# 2_MCU.net
KiCad netlist of a schematic drawn in Altium Designer
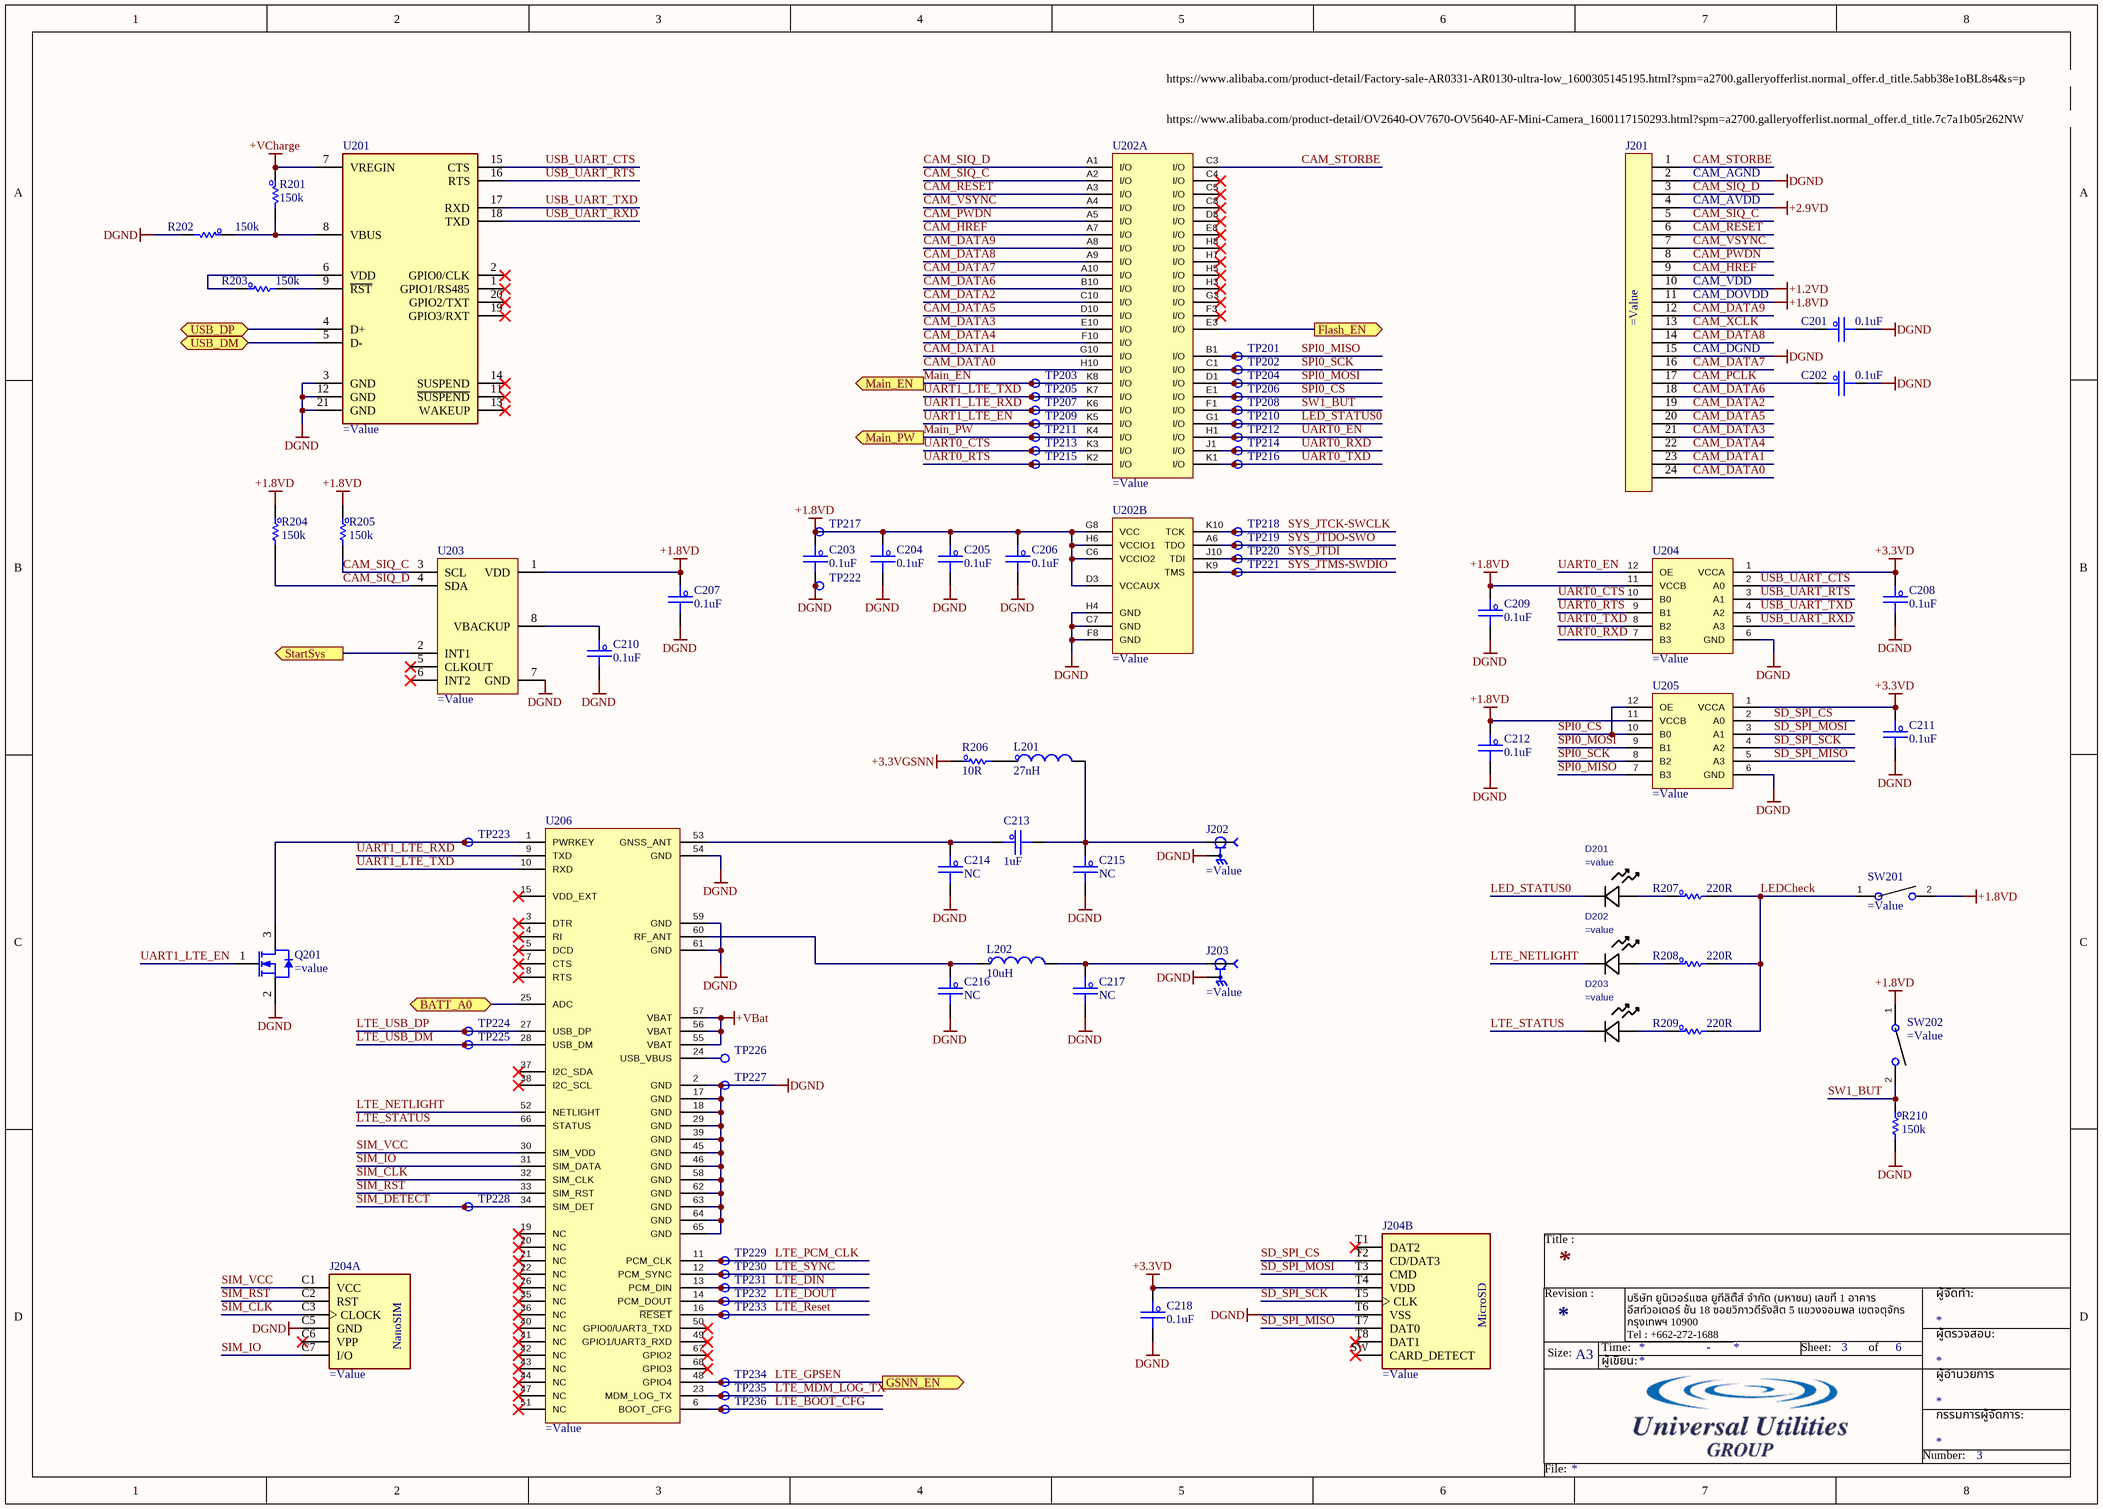
[diagram p0: 2_MCU.SchDoc]

(export (version "E")
  (design (tool "Eeschema 10.0.6"))
  (components
    (comp (ref "C201")
      (value "0.1uF")
      (footprint "C_0603")
      (description "CAP CER 0.1UF 50V X7R 0603")
      (fields (field (name "MANUFACTURER") "KEMET") (field (name "PARTNUMBER") "C0603C104K5RACTU"))
      (libsource (lib "UUSymbol") (part "C_Capacitor"))
    )
    (comp (ref "C202")
      (value "0.1uF")
      (footprint "C_0603")
      (description "CAP CER 0.1UF 50V X7R 0603")
      (fields (field (name "MANUFACTURER") "KEMET") (field (name "PARTNUMBER") "C0603C104K5RACTU"))
      (libsource (lib "UUSymbol") (part "C_Capacitor"))
    )
    (comp (ref "C203")
      (value "0.1uF")
      (footprint "C_0603")
      (description "CAP CER 0.1UF 50V X7R 0603")
      (fields (field (name "MANUFACTURER") "KEMET") (field (name "PARTNUMBER") "C0603C104K5RACTU"))
      (libsource (lib "UUSymbol") (part "C_Capacitor"))
    )
    (comp (ref "C204")
      (value "0.1uF")
      (footprint "C_0603")
      (description "CAP CER 0.1UF 50V X7R 0603")
      (fields (field (name "MANUFACTURER") "KEMET") (field (name "PARTNUMBER") "C0603C104K5RACTU"))
      (libsource (lib "UUSymbol") (part "C_Capacitor"))
    )
    (comp (ref "C205")
      (value "0.1uF")
      (footprint "C_0603")
      (description "CAP CER 0.1UF 50V X7R 0603")
      (fields (field (name "MANUFACTURER") "KEMET") (field (name "PARTNUMBER") "C0603C104K5RACTU"))
      (libsource (lib "UUSymbol") (part "C_Capacitor"))
    )
    (comp (ref "C206")
      (value "0.1uF")
      (footprint "C_0603")
      (description "CAP CER 0.1UF 50V X7R 0603")
      (fields (field (name "MANUFACTURER") "KEMET") (field (name "PARTNUMBER") "C0603C104K5RACTU"))
      (libsource (lib "UUSymbol") (part "C_Capacitor"))
    )
    (comp (ref "C207")
      (value "0.1uF")
      (footprint "C_0603")
      (description "CAP CER 0.1UF 50V X7R 0603")
      (fields (field (name "MANUFACTURER") "KEMET") (field (name "PARTNUMBER") "C0603C104K5RACTU"))
      (libsource (lib "UUSymbol") (part "C_Capacitor"))
    )
    (comp (ref "C208")
      (value "0.1uF")
      (footprint "C_0603")
      (description "CAP CER 0.1UF 50V X7R 0603")
      (fields (field (name "MANUFACTURER") "KEMET") (field (name "PARTNUMBER") "C0603C104K5RACTU"))
      (libsource (lib "UUSymbol") (part "C_Capacitor"))
    )
    (comp (ref "C209")
      (value "0.1uF")
      (footprint "C_0603")
      (description "CAP CER 0.1UF 50V X7R 0603")
      (fields (field (name "MANUFACTURER") "KEMET") (field (name "PARTNUMBER") "C0603C104K5RACTU"))
      (libsource (lib "UUSymbol") (part "C_Capacitor"))
    )
    (comp (ref "C210")
      (value "0.1uF")
      (footprint "C_0603")
      (description "CAP CER 0.1UF 50V X7R 0603")
      (fields (field (name "MANUFACTURER") "KEMET") (field (name "PARTNUMBER") "C0603C104K5RACTU"))
      (libsource (lib "UUSymbol") (part "C_Capacitor"))
    )
    (comp (ref "C211")
      (value "0.1uF")
      (footprint "C_0603")
      (description "CAP CER 0.1UF 50V X7R 0603")
      (fields (field (name "MANUFACTURER") "KEMET") (field (name "PARTNUMBER") "C0603C104K5RACTU"))
      (libsource (lib "UUSymbol") (part "C_Capacitor"))
    )
    (comp (ref "C212")
      (value "0.1uF")
      (footprint "C_0603")
      (description "CAP CER 0.1UF 50V X7R 0603")
      (fields (field (name "MANUFACTURER") "KEMET") (field (name "PARTNUMBER") "C0603C104K5RACTU"))
      (libsource (lib "UUSymbol") (part "C_Capacitor"))
    )
    (comp (ref "C213")
      (value "1uF")
      (footprint "C_0603")
      (description "Capacitor")
      (libsource (lib "UUSymbol") (part "C_Capacitor"))
    )
    (comp (ref "C214")
      (value "NC")
      (footprint "C_0603")
      (description "Capacitor")
      (libsource (lib "UUSymbol") (part "C_Capacitor"))
    )
    (comp (ref "C215")
      (value "NC")
      (footprint "C_0603")
      (description "Capacitor")
      (libsource (lib "UUSymbol") (part "C_Capacitor"))
    )
    (comp (ref "C216")
      (value "NC")
      (footprint "C_0603")
      (description "Capacitor")
      (libsource (lib "UUSymbol") (part "C_Capacitor"))
    )
    (comp (ref "C217")
      (value "NC")
      (footprint "C_0603")
      (description "Capacitor")
      (libsource (lib "UUSymbol") (part "C_Capacitor"))
    )
    (comp (ref "C218")
      (value "0.1uF")
      (footprint "C_0603")
      (description "CAP CER 0.1UF 50V X7R 0603")
      (fields (field (name "MANUFACTURER") "KEMET") (field (name "PARTNUMBER") "C0603C104K5RACTU"))
      (libsource (lib "UUSymbol") (part "C_Capacitor"))
    )
    (comp (ref "D201")
      (value "~")
      (footprint "LED_0VS75000_WRE")
      (description "LED BLUE CLEAR 0603 SMD")
      (fields (field (name "MANUFACTURER") "Wurth Electronics") (field (name "PARTNUMBER") "150060VS75000"))
      (libsource (lib "UUSymbol") (part "D_LED_150060BS75000"))
    )
    (comp (ref "D202")
      (value "~")
      (footprint "LED_0VS75000_WRE")
      (description "LED BLUE CLEAR 0603 SMD")
      (fields (field (name "MANUFACTURER") "Wurth Electronics") (field (name "PARTNUMBER") "150060VS75000"))
      (libsource (lib "UUSymbol") (part "D_LED_150060BS75000"))
    )
    (comp (ref "D203")
      (value "~")
      (footprint "LED_0VS75000_WRE")
      (description "LED BLUE CLEAR 0603 SMD")
      (fields (field (name "MANUFACTURER") "Wurth Electronics") (field (name "PARTNUMBER") "150060VS75000"))
      (libsource (lib "UUSymbol") (part "D_LED_150060BS75000"))
    )
    (comp (ref "J201")
      (value "~")
      (footprint "PANASONIC_AYF532435")
      (description "CONN FFC FPC 24POS 0.50MM R/A")
      (fields
        (field (name "PARTNUMBER") "AYF532435")
        (field (name "MANUFACTURER") "Panasonic Electric Works")
      )
      (libsource (lib "UUSymbol") (part "CON_24P"))
    )
    (comp (ref "J202")
      (value "~")
      (footprint "MOLEX_0734120114")
      (description "CONN UMC RCPT STR 50 OHM SMD")
      (fields (field (name "PARTNUMBER") "0734120114") (field (name "MANUFACTURER") "Molex"))
      (libsource (lib "UUSymbol") (part "CON_U.FL"))
    )
    (comp (ref "J203")
      (value "~")
      (footprint "MOLEX_0734120114")
      (description "CONN UMC RCPT STR 50 OHM SMD")
      (fields (field (name "PARTNUMBER") "0734120114") (field (name "MANUFACTURER") "Molex"))
      (libsource (lib "UUSymbol") (part "CON_U.FL"))
    )
    (comp (ref "J204")
      (value "~")
      (footprint "MOLEX_1042391430")
      (description "IC CPLD 64MC 4.6NS 56BGA")
      (fields (field (name "PARTNUMBER") "XC2C64A-5CP56C") (field (name "MANUFACTURER") "AMD Xilinx"))
      (libsource (lib "UUSymbol") (part "CON_SIMSD_1042391430"))
    )
    (comp (ref "L201")
      (value "27nH")
      (footprint "L_0603")
      (description "10µH Shielded Multilayer Inductor 250mA 1.05Ohm 0603 (1608 Metric)")
      (fields (field (name "MANUFACTURER") "TDK Corporation") (field (name "PARTNUMBER") "MLZ1608M100WT000"))
      (libsource (lib "UUSymbol") (part "L_Inductor"))
    )
    (comp (ref "L202")
      (value "10uH")
      (footprint "L_0603")
      (description "10µH Shielded Multilayer Inductor 250mA 1.05Ohm 0603 (1608 Metric)")
      (fields (field (name "MANUFACTURER") "TDK Corporation") (field (name "PARTNUMBER") "MLZ1608M100WT000"))
      (libsource (lib "UUSymbol") (part "L_Inductor"))
    )
    (comp (ref "Q201")
      (value "~")
      (footprint "SOT95P245X110-3M")
      (description "MOSFET N-CH 60V 300MA SOT23-3")
      (fields
        (field (name "MANUFACTURER") "Infineon Technologies")
        (field (name "PARTNUMBER") "2N7002H6327XTSA2")
      )
      (libsource (lib "UUSymbol") (part "Q_NMOS_2N7002H"))
    )
    (comp (ref "R201")
      (value "150k")
      (footprint "R_0603")
      (description "RES SMD 150K OHM 1% 1/10W 0603")
      (fields (field (name "MANUFACTURER") "Vishay Dale") (field (name "PARTNUMBER") "CRCW0603150KFKEAC"))
      (libsource (lib "UUSymbol") (part "R_Resister"))
    )
    (comp (ref "R202")
      (value "150k")
      (footprint "R_0603")
      (description "RES SMD 150K OHM 1% 1/10W 0603")
      (fields (field (name "MANUFACTURER") "Vishay Dale") (field (name "PARTNUMBER") "CRCW0603150KFKEAC"))
      (libsource (lib "UUSymbol") (part "R_Resister"))
    )
    (comp (ref "R203")
      (value "150k")
      (footprint "R_0603")
      (description "RES SMD 150K OHM 1% 1/10W 0603")
      (fields (field (name "MANUFACTURER") "Vishay Dale") (field (name "PARTNUMBER") "CRCW0603150KFKEAC"))
      (libsource (lib "UUSymbol") (part "R_Resister"))
    )
    (comp (ref "R204")
      (value "150k")
      (footprint "R_0603")
      (description "RES SMD 150K OHM 1% 1/10W 0603")
      (fields (field (name "MANUFACTURER") "Vishay Dale") (field (name "PARTNUMBER") "CRCW0603150KFKEAC"))
      (libsource (lib "UUSymbol") (part "R_Resister"))
    )
    (comp (ref "R205")
      (value "150k")
      (footprint "R_0603")
      (description "RES SMD 150K OHM 1% 1/10W 0603")
      (fields (field (name "MANUFACTURER") "Vishay Dale") (field (name "PARTNUMBER") "CRCW0603150KFKEAC"))
      (libsource (lib "UUSymbol") (part "R_Resister"))
    )
    (comp (ref "R206")
      (value "10R")
      (footprint "R_0603")
      (description "Resistor")
      (fields (field (name "MANUFACTURER") "Vishay") (field (name "PARTNUMBER") "EXB-2HV472JV"))
      (libsource (lib "UUSymbol") (part "R_Resister"))
    )
    (comp (ref "R207")
      (value "220R")
      (footprint "R_0603")
      (description "RES SMD 220 OHM 1% 1/10W 0603")
      (fields (field (name "MANUFACTURER") "Vishay Dale") (field (name "PARTNUMBER") "CRCW0603220RFKEAC"))
      (libsource (lib "UUSymbol") (part "R_Resister"))
    )
    (comp (ref "R208")
      (value "220R")
      (footprint "R_0603")
      (description "RES SMD 220 OHM 1% 1/10W 0603")
      (fields (field (name "MANUFACTURER") "Vishay Dale") (field (name "PARTNUMBER") "CRCW0603220RFKEAC"))
      (libsource (lib "UUSymbol") (part "R_Resister"))
    )
    (comp (ref "R209")
      (value "220R")
      (footprint "R_0603")
      (description "RES SMD 220 OHM 1% 1/10W 0603")
      (fields (field (name "MANUFACTURER") "Vishay Dale") (field (name "PARTNUMBER") "CRCW0603220RFKEAC"))
      (libsource (lib "UUSymbol") (part "R_Resister"))
    )
    (comp (ref "R210")
      (value "150k")
      (footprint "R_0603")
      (description "RES SMD 150K OHM 1% 1/10W 0603")
      (fields (field (name "MANUFACTURER") "Vishay Dale") (field (name "PARTNUMBER") "CRCW0603150KFKEAC"))
      (libsource (lib "UUSymbol") (part "R_Resister"))
    )
    (comp (ref "SW201")
      (value "~")
      (footprint "SW_KSS241GLFS_CN")
      (description "SWITCH TACTILE SPST-NO 0.05A 50V")
      (fields (field (name "PARTNUMBER") "KSS241GLFS") (field (name "MANUFACTURER") "C&K"))
      (libsource (lib "UUSymbol") (part "SW_TAC"))
    )
    (comp (ref "SW202")
      (value "~")
      (footprint "SW_KSS241GLFS_CN")
      (description "SWITCH TACTILE SPST-NO 0.05A 50V")
      (fields (field (name "PARTNUMBER") "KSS241GLFS") (field (name "MANUFACTURER") "C&K"))
      (libsource (lib "UUSymbol") (part "SW_TAC"))
    )
    (comp (ref "TP201")
      (value "~")
      (footprint "TP_Testpoint")
      (description "TestPoint")
      (libsource (lib "UUSymbol") (part "TP_TestPoint"))
    )
    (comp (ref "TP202")
      (value "~")
      (footprint "TP_Testpoint")
      (description "TestPoint")
      (libsource (lib "UUSymbol") (part "TP_TestPoint"))
    )
    (comp (ref "TP203")
      (value "~")
      (footprint "TP_Testpoint")
      (description "TestPoint")
      (libsource (lib "UUSymbol") (part "TP_TestPoint"))
    )
    (comp (ref "TP204")
      (value "~")
      (footprint "TP_Testpoint")
      (description "TestPoint")
      (libsource (lib "UUSymbol") (part "TP_TestPoint"))
    )
    (comp (ref "TP205")
      (value "~")
      (footprint "TP_Testpoint")
      (description "TestPoint")
      (libsource (lib "UUSymbol") (part "TP_TestPoint"))
    )
    (comp (ref "TP206")
      (value "~")
      (footprint "TP_Testpoint")
      (description "TestPoint")
      (libsource (lib "UUSymbol") (part "TP_TestPoint"))
    )
    (comp (ref "TP207")
      (value "~")
      (footprint "TP_Testpoint")
      (description "TestPoint")
      (libsource (lib "UUSymbol") (part "TP_TestPoint"))
    )
    (comp (ref "TP208")
      (value "~")
      (footprint "TP_Testpoint")
      (description "TestPoint")
      (libsource (lib "UUSymbol") (part "TP_TestPoint"))
    )
    (comp (ref "TP209")
      (value "~")
      (footprint "TP_Testpoint")
      (description "TestPoint")
      (libsource (lib "UUSymbol") (part "TP_TestPoint"))
    )
    (comp (ref "TP210")
      (value "~")
      (footprint "TP_Testpoint")
      (description "TestPoint")
      (libsource (lib "UUSymbol") (part "TP_TestPoint"))
    )
    (comp (ref "TP211")
      (value "~")
      (footprint "TP_Testpoint")
      (description "TestPoint")
      (libsource (lib "UUSymbol") (part "TP_TestPoint"))
    )
    (comp (ref "TP212")
      (value "~")
      (footprint "TP_Testpoint")
      (description "TestPoint")
      (libsource (lib "UUSymbol") (part "TP_TestPoint"))
    )
    (comp (ref "TP213")
      (value "~")
      (footprint "TP_Testpoint")
      (description "TestPoint")
      (libsource (lib "UUSymbol") (part "TP_TestPoint"))
    )
    (comp (ref "TP214")
      (value "~")
      (footprint "TP_Testpoint")
      (description "TestPoint")
      (libsource (lib "UUSymbol") (part "TP_TestPoint"))
    )
    (comp (ref "TP215")
      (value "~")
      (footprint "TP_Testpoint")
      (description "TestPoint")
      (libsource (lib "UUSymbol") (part "TP_TestPoint"))
    )
    (comp (ref "TP216")
      (value "~")
      (footprint "TP_Testpoint")
      (description "TestPoint")
      (libsource (lib "UUSymbol") (part "TP_TestPoint"))
    )
    (comp (ref "TP217")
      (value "~")
      (footprint "TP_Testpoint")
      (description "TestPoint")
      (libsource (lib "UUSymbol") (part "TP_TestPoint"))
    )
    (comp (ref "TP218")
      (value "~")
      (footprint "TP_Testpoint")
      (description "TestPoint")
      (libsource (lib "UUSymbol") (part "TP_TestPoint"))
    )
    (comp (ref "TP219")
      (value "~")
      (footprint "TP_Testpoint")
      (description "TestPoint")
      (libsource (lib "UUSymbol") (part "TP_TestPoint"))
    )
    (comp (ref "TP220")
      (value "~")
      (footprint "TP_Testpoint")
      (description "TestPoint")
      (libsource (lib "UUSymbol") (part "TP_TestPoint"))
    )
    (comp (ref "TP221")
      (value "~")
      (footprint "TP_Testpoint")
      (description "TestPoint")
      (libsource (lib "UUSymbol") (part "TP_TestPoint"))
    )
    (comp (ref "TP222")
      (value "~")
      (footprint "TP_Testpoint")
      (description "TestPoint")
      (libsource (lib "UUSymbol") (part "TP_TestPoint"))
    )
    (comp (ref "TP223")
      (value "~")
      (footprint "TP_Testpoint")
      (description "TestPoint")
      (libsource (lib "UUSymbol") (part "TP_TestPoint"))
    )
    (comp (ref "TP224")
      (value "~")
      (footprint "TP_Testpoint")
      (description "TestPoint")
      (libsource (lib "UUSymbol") (part "TP_TestPoint"))
    )
    (comp (ref "TP225")
      (value "~")
      (footprint "TP_Testpoint")
      (description "TestPoint")
      (libsource (lib "UUSymbol") (part "TP_TestPoint"))
    )
    (comp (ref "TP226")
      (value "~")
      (footprint "TP_Testpoint")
      (description "TestPoint")
      (libsource (lib "UUSymbol") (part "TP_TestPoint"))
    )
    (comp (ref "TP227")
      (value "~")
      (footprint "TP_Testpoint")
      (description "TestPoint")
      (libsource (lib "UUSymbol") (part "TP_TestPoint"))
    )
    (comp (ref "TP228")
      (value "~")
      (footprint "TP_Testpoint")
      (description "TestPoint")
      (libsource (lib "UUSymbol") (part "TP_TestPoint"))
    )
    (comp (ref "TP229")
      (value "~")
      (footprint "TP_Testpoint")
      (description "TestPoint")
      (libsource (lib "UUSymbol") (part "TP_TestPoint"))
    )
    (comp (ref "TP230")
      (value "~")
      (footprint "TP_Testpoint")
      (description "TestPoint")
      (libsource (lib "UUSymbol") (part "TP_TestPoint"))
    )
    (comp (ref "TP231")
      (value "~")
      (footprint "TP_Testpoint")
      (description "TestPoint")
      (libsource (lib "UUSymbol") (part "TP_TestPoint"))
    )
    (comp (ref "TP232")
      (value "~")
      (footprint "TP_Testpoint")
      (description "TestPoint")
      (libsource (lib "UUSymbol") (part "TP_TestPoint"))
    )
    (comp (ref "TP233")
      (value "~")
      (footprint "TP_Testpoint")
      (description "TestPoint")
      (libsource (lib "UUSymbol") (part "TP_TestPoint"))
    )
    (comp (ref "TP234")
      (value "~")
      (footprint "TP_Testpoint")
      (description "TestPoint")
      (libsource (lib "UUSymbol") (part "TP_TestPoint"))
    )
    (comp (ref "TP235")
      (value "~")
      (footprint "TP_Testpoint")
      (description "TestPoint")
      (libsource (lib "UUSymbol") (part "TP_TestPoint"))
    )
    (comp (ref "TP236")
      (value "~")
      (footprint "TP_Testpoint")
      (description "TestPoint")
      (libsource (lib "UUSymbol") (part "TP_TestPoint"))
    )
    (comp (ref "U201")
      (value "~")
      (footprint "SILABS_CP2102N-A02-GQFN20R")
      (description "IC USB TO UART BRIDGE QFN20")
      (fields (field (name "PARTNUMBER") "CP2102N-A02-GQFN20") (field (name "MANUFACTURER") "Silicon Labs"))
      (libsource (lib "UUSymbol") (part "IC_USB_CP2102N"))
    )
    (comp (ref "U202")
      (value "~")
      (footprint "CP56_XIL_XC2C64A-5CPG56C")
      (description "IC CPLD 64MC 4.6NS 56BGA")
      (fields (field (name "PARTNUMBER") "XC2C64A-5CP56C") (field (name "MANUFACTURER") "AMD Xilinx"))
      (libsource (lib "UUSymbol") (part "IC_FPGA_XC2C64A"))
    )
    (comp (ref "U203")
      (value "~")
      (footprint "RV8523C3")
      (description "IC RTC CLK/CALENDAR I2C 10SON")
      (fields
        (field (name "PARTNUMBER") "RV-8523-C3-32.768KHZ-20PPM-TA-QC")
        (field (name "MANUFACTURER") "Micro Crystal AG")
      )
      (libsource (lib "UUSymbol") (part "IC_RTC_RV-8523-C3"))
    )
    (comp (ref "U204")
      (value "~")
      (footprint "UMLP12_1P7X2_O00")
      (description "IC TRNSLTR BIDIRECTIONAL 12MLP")
      (fields (field (name "PARTNUMBER") "FXLA0104QFX-F106") (field (name "MANUFACTURER") "onsemi"))
      (libsource (lib "UUSymbol") (part "IC_TRAN_FXLA0104X"))
    )
    (comp (ref "U205")
      (value "~")
      (footprint "UMLP12_1P7X2_O00")
      (description "IC TRNSLTR BIDIRECTIONAL 12MLP")
      (fields (field (name "PARTNUMBER") "FXLA0104QFX-F106") (field (name "MANUFACTURER") "onsemi"))
      (libsource (lib "UUSymbol") (part "IC_TRAN_FXLA0104X"))
    )
    (comp (ref "U206")
      (value "~")
      (footprint "SIM7000A S2-1000")
      (description "DGTL ISO 5000VRMS 6CH 16SOIC")
      (fields
        (field (name "MANUFACTURER") "SIMCom Wireless Solutions Limited")
        (field (name "PARTNUMBER") "SIM7000G")
      )
      (libsource (lib "UUSymbol") (part "IC_MOD_SIM7000X"))
    )
  )
  (nets
    (net (code "1") (name "+1.2VD") (class "Default")
      (node (ref "J201") (pin "10") (pinfunction "10_10") (pintype "passive"))
    )
    (net (code "2") (name "+1.8VD") (class "Default")
      (node (ref "C203") (pin "1") (pinfunction "1_1") (pintype "passive"))
      (node (ref "C204") (pin "1") (pinfunction "1_1") (pintype "passive"))
      (node (ref "C205") (pin "1") (pinfunction "1_1") (pintype "passive"))
      (node (ref "C206") (pin "1") (pinfunction "1_1") (pintype "passive"))
      (node (ref "C207") (pin "1") (pinfunction "1_1") (pintype "passive"))
      (node (ref "C209") (pin "1") (pinfunction "1_1") (pintype "passive"))
      (node (ref "C212") (pin "1") (pinfunction "1_1") (pintype "passive"))
      (node (ref "J201") (pin "11") (pinfunction "11_11") (pintype "passive"))
      (node (ref "R204") (pin "1") (pinfunction "1_1") (pintype "passive"))
      (node (ref "R205") (pin "1") (pinfunction "1_1") (pintype "passive"))
      (node (ref "SW201") (pin "2") (pinfunction "2_2") (pintype "passive"))
      (node (ref "SW202") (pin "1") (pinfunction "1_1") (pintype "passive"))
      (node (ref "TP217") (pin "1") (pinfunction "1_1") (pintype "passive"))
      (node (ref "U202") (pin "C6") (pinfunction "VCCIO2_C6") (pintype "passive"))
      (node (ref "U202") (pin "D3") (pinfunction "VCCAUX_D3") (pintype "passive"))
      (node (ref "U202") (pin "G8") (pinfunction "VCC_G8") (pintype "passive"))
      (node (ref "U202") (pin "H6") (pinfunction "VCCIO1_H6") (pintype "passive"))
      (node (ref "U203") (pin "1") (pinfunction "VDD_1") (pintype "passive"))
      (node (ref "U204") (pin "11") (pinfunction "VCCB_11") (pintype "passive"))
      (node (ref "U205") (pin "11") (pinfunction "VCCB_11") (pintype "passive"))
    )
    (net (code "3") (name "+2.9VD") (class "Default")
      (node (ref "J201") (pin "4") (pinfunction "4_4") (pintype "passive"))
    )
    (net (code "4") (name "+3.3VD") (class "Default")
      (node (ref "C208") (pin "1") (pinfunction "1_1") (pintype "passive"))
      (node (ref "C211") (pin "1") (pinfunction "1_1") (pintype "passive"))
      (node (ref "C218") (pin "1") (pinfunction "1_1") (pintype "passive"))
      (node (ref "J204") (pin "T4") (pinfunction "VDD_T4") (pintype "passive"))
      (node (ref "U204") (pin "1") (pinfunction "VCCA_1") (pintype "passive"))
      (node (ref "U205") (pin "1") (pinfunction "VCCA_1") (pintype "passive"))
    )
    (net (code "5") (name "+3.3VGSNN") (class "Default")
      (node (ref "R206") (pin "1") (pinfunction "1_1") (pintype "passive"))
    )
    (net (code "6") (name "+VBat") (class "Default")
      (node (ref "U206") (pin "55") (pinfunction "VBAT_55") (pintype "passive"))
      (node (ref "U206") (pin "56") (pinfunction "VBAT_56") (pintype "passive"))
      (node (ref "U206") (pin "57") (pinfunction "VBAT_57") (pintype "passive"))
    )
    (net (code "7") (name "+VCharge") (class "Default")
      (node (ref "R201") (pin "1") (pinfunction "1_1") (pintype "passive"))
      (node (ref "U201") (pin "7") (pinfunction "VREGIN_7") (pintype "passive"))
    )
    (net (code "8") (name "/BATT_A0") (class "Default")
      (node (ref "U206") (pin "25") (pinfunction "ADC_25") (pintype "passive"))
    )
    (net (code "9") (name "/CAM_DATA0") (class "Default")
      (node (ref "J201") (pin "24") (pinfunction "24_24") (pintype "passive"))
      (node (ref "U202") (pin "H10") (pinfunction "I/O_H10") (pintype "passive"))
    )
    (net (code "10") (name "/CAM_DATA1") (class "Default")
      (node (ref "J201") (pin "23") (pinfunction "23_23") (pintype "passive"))
      (node (ref "U202") (pin "G10") (pinfunction "I/O_G10") (pintype "passive"))
    )
    (net (code "11") (name "/CAM_DATA2") (class "Default")
      (node (ref "J201") (pin "19") (pinfunction "19_19") (pintype "passive"))
      (node (ref "U202") (pin "C10") (pinfunction "I/O_C10") (pintype "passive"))
    )
    (net (code "12") (name "/CAM_DATA3") (class "Default")
      (node (ref "J201") (pin "21") (pinfunction "21_21") (pintype "passive"))
      (node (ref "U202") (pin "E10") (pinfunction "I/O_E10") (pintype "passive"))
    )
    (net (code "13") (name "/CAM_DATA4") (class "Default")
      (node (ref "J201") (pin "22") (pinfunction "22_22") (pintype "passive"))
      (node (ref "U202") (pin "F10") (pinfunction "I/O_F10") (pintype "passive"))
    )
    (net (code "14") (name "/CAM_DATA5") (class "Default")
      (node (ref "J201") (pin "20") (pinfunction "20_20") (pintype "passive"))
      (node (ref "U202") (pin "D10") (pinfunction "I/O_D10") (pintype "passive"))
    )
    (net (code "15") (name "/CAM_DATA6") (class "Default")
      (node (ref "J201") (pin "18") (pinfunction "18_18") (pintype "passive"))
      (node (ref "U202") (pin "B10") (pinfunction "I/O_B10") (pintype "passive"))
    )
    (net (code "16") (name "/CAM_DATA7") (class "Default")
      (node (ref "J201") (pin "16") (pinfunction "16_16") (pintype "passive"))
      (node (ref "U202") (pin "A10") (pinfunction "I/O_A10") (pintype "passive"))
    )
    (net (code "17") (name "/CAM_DATA8") (class "Default")
      (node (ref "J201") (pin "14") (pinfunction "14_14") (pintype "passive"))
      (node (ref "U202") (pin "A9") (pinfunction "I/O_A9") (pintype "passive"))
    )
    (net (code "18") (name "/CAM_DATA9") (class "Default")
      (node (ref "J201") (pin "12") (pinfunction "12_12") (pintype "passive"))
      (node (ref "U202") (pin "A8") (pinfunction "I/O_A8") (pintype "passive"))
    )
    (net (code "19") (name "/CAM_HREF") (class "Default")
      (node (ref "J201") (pin "9") (pinfunction "9_9") (pintype "passive"))
      (node (ref "U202") (pin "A7") (pinfunction "I/O_A7") (pintype "passive"))
    )
    (net (code "20") (name "/CAM_PCLK") (class "Default")
      (node (ref "C202") (pin "1") (pinfunction "1_1") (pintype "passive"))
      (node (ref "J201") (pin "17") (pinfunction "17_17") (pintype "passive"))
    )
    (net (code "21") (name "/CAM_PWDN") (class "Default")
      (node (ref "J201") (pin "8") (pinfunction "8_8") (pintype "passive"))
      (node (ref "U202") (pin "A5") (pinfunction "I/O_A5") (pintype "passive"))
    )
    (net (code "22") (name "/CAM_RESET") (class "Default")
      (node (ref "J201") (pin "6") (pinfunction "6_6") (pintype "passive"))
      (node (ref "U202") (pin "A3") (pinfunction "I/O_A3") (pintype "passive"))
    )
    (net (code "23") (name "/CAM_SIQ_C") (class "Default")
      (node (ref "J201") (pin "5") (pinfunction "5_5") (pintype "passive"))
      (node (ref "R205") (pin "2") (pinfunction "2_2") (pintype "passive"))
      (node (ref "U202") (pin "A2") (pinfunction "I/O_A2") (pintype "passive"))
      (node (ref "U203") (pin "3") (pinfunction "SCL_3") (pintype "passive"))
    )
    (net (code "24") (name "/CAM_SIQ_D") (class "Default")
      (node (ref "J201") (pin "3") (pinfunction "3_3") (pintype "passive"))
      (node (ref "R204") (pin "2") (pinfunction "2_2") (pintype "passive"))
      (node (ref "U202") (pin "A1") (pinfunction "I/O_A1") (pintype "passive"))
      (node (ref "U203") (pin "4") (pinfunction "SDA_4") (pintype "passive"))
    )
    (net (code "25") (name "/CAM_STORBE") (class "Default")
      (node (ref "J201") (pin "1") (pinfunction "1_1") (pintype "passive"))
      (node (ref "U202") (pin "C3") (pinfunction "I/O_C3") (pintype "passive"))
    )
    (net (code "26") (name "/CAM_VSYNC") (class "Default")
      (node (ref "J201") (pin "7") (pinfunction "7_7") (pintype "passive"))
      (node (ref "U202") (pin "A4") (pinfunction "I/O_A4") (pintype "passive"))
    )
    (net (code "27") (name "/CAM_XCLK") (class "Default")
      (node (ref "C201") (pin "1") (pinfunction "1_1") (pintype "passive"))
      (node (ref "J201") (pin "13") (pinfunction "13_13") (pintype "passive"))
    )
    (net (code "28") (name "/Flash_EN") (class "Default")
      (node (ref "U202") (pin "E3") (pinfunction "I/O_E3") (pintype "passive"))
    )
    (net (code "29") (name "/LEDCheck") (class "Default")
      (node (ref "R207") (pin "2") (pinfunction "2_2") (pintype "passive"))
      (node (ref "R208") (pin "2") (pinfunction "2_2") (pintype "passive"))
      (node (ref "R209") (pin "2") (pinfunction "2_2") (pintype "passive"))
      (node (ref "SW201") (pin "1") (pinfunction "1_1") (pintype "passive"))
    )
    (net (code "30") (name "/LED_STATUS0") (class "Default")
      (node (ref "D201") (pin "2") (pinfunction "2_2") (pintype "passive"))
      (node (ref "TP210") (pin "1") (pinfunction "1_1") (pintype "passive"))
      (node (ref "U202") (pin "G1") (pinfunction "I/O_G1") (pintype "passive"))
    )
    (net (code "31") (name "/LTE_BOOT_CFG") (class "Default")
      (node (ref "TP236") (pin "1") (pinfunction "1_1") (pintype "passive"))
      (node (ref "U206") (pin "6") (pinfunction "BOOT_CFG_6") (pintype "passive"))
    )
    (net (code "32") (name "/LTE_DIN") (class "Default")
      (node (ref "TP231") (pin "1") (pinfunction "1_1") (pintype "passive"))
      (node (ref "U206") (pin "13") (pinfunction "PCM_DIN_13") (pintype "passive"))
    )
    (net (code "33") (name "/LTE_DOUT") (class "Default")
      (node (ref "TP232") (pin "1") (pinfunction "1_1") (pintype "passive"))
      (node (ref "U206") (pin "14") (pinfunction "PCM_DOUT_14") (pintype "passive"))
    )
    (net (code "34") (name "/LTE_GPSEN") (class "Default")
      (node (ref "TP234") (pin "1") (pinfunction "1_1") (pintype "passive"))
      (node (ref "U206") (pin "48") (pinfunction "GPIO4_48") (pintype "passive"))
    )
    (net (code "35") (name "/LTE_MDM_LOG_TX") (class "Default")
      (node (ref "TP235") (pin "1") (pinfunction "1_1") (pintype "passive"))
      (node (ref "U206") (pin "23") (pinfunction "MDM_LOG_TX_23") (pintype "passive"))
    )
    (net (code "36") (name "/LTE_NETLIGHT") (class "Default")
      (node (ref "D202") (pin "2") (pinfunction "2_2") (pintype "passive"))
      (node (ref "U206") (pin "52") (pinfunction "NETLIGHT_52") (pintype "passive"))
    )
    (net (code "37") (name "/LTE_PCM_CLK") (class "Default")
      (node (ref "TP229") (pin "1") (pinfunction "1_1") (pintype "passive"))
      (node (ref "U206") (pin "11") (pinfunction "PCM_CLK_11") (pintype "passive"))
    )
    (net (code "38") (name "/LTE_Reset") (class "Default")
      (node (ref "TP233") (pin "1") (pinfunction "1_1") (pintype "passive"))
      (node (ref "U206") (pin "16") (pinfunction "~{RESET}_16") (pintype "passive"))
    )
    (net (code "39") (name "/LTE_STATUS") (class "Default")
      (node (ref "D203") (pin "2") (pinfunction "2_2") (pintype "passive"))
      (node (ref "U206") (pin "66") (pinfunction "STATUS_66") (pintype "passive"))
    )
    (net (code "40") (name "/LTE_SYNC") (class "Default")
      (node (ref "TP230") (pin "1") (pinfunction "1_1") (pintype "passive"))
      (node (ref "U206") (pin "12") (pinfunction "PCM_SYNC_12") (pintype "passive"))
    )
    (net (code "41") (name "/LTE_USB_DM") (class "Default")
      (node (ref "TP225") (pin "1") (pinfunction "1_1") (pintype "passive"))
      (node (ref "U206") (pin "28") (pinfunction "USB_DM_28") (pintype "passive"))
    )
    (net (code "42") (name "/LTE_USB_DP") (class "Default")
      (node (ref "TP224") (pin "1") (pinfunction "1_1") (pintype "passive"))
      (node (ref "U206") (pin "27") (pinfunction "USB_DP_27") (pintype "passive"))
    )
    (net (code "43") (name "/Main_EN") (class "Default")
      (node (ref "TP203") (pin "1") (pinfunction "1_1") (pintype "passive"))
      (node (ref "U202") (pin "K8") (pinfunction "I/O_K8") (pintype "passive"))
    )
    (net (code "44") (name "/Main_PW") (class "Default")
      (node (ref "TP211") (pin "1") (pinfunction "1_1") (pintype "passive"))
      (node (ref "U202") (pin "K4") (pinfunction "I/O_K4") (pintype "passive"))
    )
    (net (code "45") (name "/SD_SPI_CS") (class "Default")
      (node (ref "J204") (pin "T2") (pinfunction "CD/DAT3_T2") (pintype "passive"))
      (node (ref "U205") (pin "2") (pinfunction "A0_2") (pintype "passive"))
    )
    (net (code "46") (name "/SD_SPI_MISO") (class "Default")
      (node (ref "J204") (pin "T7") (pinfunction "DAT0_T7") (pintype "passive"))
      (node (ref "U205") (pin "5") (pinfunction "A3_5") (pintype "passive"))
    )
    (net (code "47") (name "/SD_SPI_MOSI") (class "Default")
      (node (ref "J204") (pin "T3") (pinfunction "CMD_T3") (pintype "passive"))
      (node (ref "U205") (pin "3") (pinfunction "A1_3") (pintype "passive"))
    )
    (net (code "48") (name "/SD_SPI_SCK") (class "Default")
      (node (ref "J204") (pin "T5") (pinfunction "CLK_T5") (pintype "passive"))
      (node (ref "U205") (pin "4") (pinfunction "A2_4") (pintype "passive"))
    )
    (net (code "49") (name "/SIM_CLK") (class "Default")
      (node (ref "J204") (pin "C3") (pinfunction "CLOCK_C3") (pintype "passive"))
      (node (ref "U206") (pin "32") (pinfunction "SIM_CLK_32") (pintype "passive"))
    )
    (net (code "50") (name "/SIM_DETECT") (class "Default")
      (node (ref "TP228") (pin "1") (pinfunction "1_1") (pintype "passive"))
      (node (ref "U206") (pin "34") (pinfunction "SIM_DET_34") (pintype "passive"))
    )
    (net (code "51") (name "/SIM_IO") (class "Default")
      (node (ref "J204") (pin "C7") (pinfunction "I/O_C7") (pintype "passive"))
      (node (ref "U206") (pin "31") (pinfunction "SIM_DATA_31") (pintype "passive"))
    )
    (net (code "52") (name "/SIM_RST") (class "Default")
      (node (ref "J204") (pin "C2") (pinfunction "RST_C2") (pintype "passive"))
      (node (ref "U206") (pin "33") (pinfunction "SIM_RST_33") (pintype "passive"))
    )
    (net (code "53") (name "/SIM_VCC") (class "Default")
      (node (ref "J204") (pin "C1") (pinfunction "VCC_C1") (pintype "passive"))
      (node (ref "U206") (pin "30") (pinfunction "SIM_VDD_30") (pintype "passive"))
    )
    (net (code "54") (name "/SPI0_CS") (class "Default")
      (node (ref "TP206") (pin "1") (pinfunction "1_1") (pintype "passive"))
      (node (ref "U202") (pin "E1") (pinfunction "I/O_E1") (pintype "passive"))
      (node (ref "U205") (pin "10") (pinfunction "B0_10") (pintype "passive"))
      (node (ref "U205") (pin "12") (pinfunction "OE_12") (pintype "passive"))
    )
    (net (code "55") (name "/SPI0_MISO") (class "Default")
      (node (ref "TP201") (pin "1") (pinfunction "1_1") (pintype "passive"))
      (node (ref "U202") (pin "B1") (pinfunction "I/O_B1") (pintype "passive"))
      (node (ref "U205") (pin "7") (pinfunction "B3_7") (pintype "passive"))
    )
    (net (code "56") (name "/SPI0_MOSI") (class "Default")
      (node (ref "TP204") (pin "1") (pinfunction "1_1") (pintype "passive"))
      (node (ref "U202") (pin "D1") (pinfunction "I/O_D1") (pintype "passive"))
      (node (ref "U205") (pin "9") (pinfunction "B1_9") (pintype "passive"))
    )
    (net (code "57") (name "/SPI0_SCK") (class "Default")
      (node (ref "TP202") (pin "1") (pinfunction "1_1") (pintype "passive"))
      (node (ref "U202") (pin "C1") (pinfunction "I/O_C1") (pintype "passive"))
      (node (ref "U205") (pin "8") (pinfunction "B2_8") (pintype "passive"))
    )
    (net (code "58") (name "/SW1_BUT") (class "Default")
      (node (ref "R210") (pin "1") (pinfunction "1_1") (pintype "passive"))
      (node (ref "SW202") (pin "2") (pinfunction "2_2") (pintype "passive"))
      (node (ref "TP208") (pin "1") (pinfunction "1_1") (pintype "passive"))
      (node (ref "U202") (pin "F1") (pinfunction "I/O_F1") (pintype "passive"))
    )
    (net (code "59") (name "/SYS_JTCK-SWCLK") (class "Default")
      (node (ref "TP218") (pin "1") (pinfunction "1_1") (pintype "passive"))
      (node (ref "U202") (pin "K10") (pinfunction "TCK_K10") (pintype "passive"))
    )
    (net (code "60") (name "/SYS_JTDI") (class "Default")
      (node (ref "TP220") (pin "1") (pinfunction "1_1") (pintype "passive"))
      (node (ref "U202") (pin "J10") (pinfunction "TDI_J10") (pintype "passive"))
    )
    (net (code "61") (name "/SYS_JTDO-SWO") (class "Default")
      (node (ref "TP219") (pin "1") (pinfunction "1_1") (pintype "passive"))
      (node (ref "U202") (pin "A6") (pinfunction "TDO_A6") (pintype "passive"))
    )
    (net (code "62") (name "/SYS_JTMS-SWDIO") (class "Default")
      (node (ref "TP221") (pin "1") (pinfunction "1_1") (pintype "passive"))
      (node (ref "U202") (pin "K9") (pinfunction "TMS_K9") (pintype "passive"))
    )
    (net (code "63") (name "/StartSys") (class "Default")
      (node (ref "U203") (pin "2") (pinfunction "INT1_2") (pintype "passive"))
    )
    (net (code "64") (name "/UART0_CTS") (class "Default")
      (node (ref "TP213") (pin "1") (pinfunction "1_1") (pintype "passive"))
      (node (ref "U202") (pin "K3") (pinfunction "I/O_K3") (pintype "passive"))
      (node (ref "U204") (pin "10") (pinfunction "B0_10") (pintype "passive"))
    )
    (net (code "65") (name "/UART0_EN") (class "Default")
      (node (ref "TP212") (pin "1") (pinfunction "1_1") (pintype "passive"))
      (node (ref "U202") (pin "H1") (pinfunction "I/O_H1") (pintype "passive"))
      (node (ref "U204") (pin "12") (pinfunction "OE_12") (pintype "passive"))
    )
    (net (code "66") (name "/UART0_RTS") (class "Default")
      (node (ref "TP215") (pin "1") (pinfunction "1_1") (pintype "passive"))
      (node (ref "U202") (pin "K2") (pinfunction "I/O_K2") (pintype "passive"))
      (node (ref "U204") (pin "9") (pinfunction "B1_9") (pintype "passive"))
    )
    (net (code "67") (name "/UART0_RXD") (class "Default")
      (node (ref "TP214") (pin "1") (pinfunction "1_1") (pintype "passive"))
      (node (ref "U202") (pin "J1") (pinfunction "I/O_J1") (pintype "passive"))
      (node (ref "U204") (pin "7") (pinfunction "B3_7") (pintype "passive"))
    )
    (net (code "68") (name "/UART0_TXD") (class "Default")
      (node (ref "TP216") (pin "1") (pinfunction "1_1") (pintype "passive"))
      (node (ref "U202") (pin "K1") (pinfunction "I/O_K1") (pintype "passive"))
      (node (ref "U204") (pin "8") (pinfunction "B2_8") (pintype "passive"))
    )
    (net (code "69") (name "/UART1_LTE_EN") (class "Default")
      (node (ref "Q201") (pin "1") (pinfunction "G_1") (pintype "passive"))
      (node (ref "TP209") (pin "1") (pinfunction "1_1") (pintype "passive"))
      (node (ref "U202") (pin "K5") (pinfunction "I/O_K5") (pintype "passive"))
    )
    (net (code "70") (name "/UART1_LTE_RXD") (class "Default")
      (node (ref "TP207") (pin "1") (pinfunction "1_1") (pintype "passive"))
      (node (ref "U202") (pin "K6") (pinfunction "I/O_K6") (pintype "passive"))
      (node (ref "U206") (pin "9") (pinfunction "TXD_9") (pintype "passive"))
    )
    (net (code "71") (name "/UART1_LTE_TXD") (class "Default")
      (node (ref "TP205") (pin "1") (pinfunction "1_1") (pintype "passive"))
      (node (ref "U202") (pin "K7") (pinfunction "I/O_K7") (pintype "passive"))
      (node (ref "U206") (pin "10") (pinfunction "RXD_10") (pintype "passive"))
    )
    (net (code "72") (name "/USB_DM") (class "Default")
      (node (ref "U201") (pin "5") (pinfunction "D-_5") (pintype "passive"))
    )
    (net (code "73") (name "/USB_DP") (class "Default")
      (node (ref "U201") (pin "4") (pinfunction "D+_4") (pintype "passive"))
    )
    (net (code "74") (name "/USB_UART_CTS") (class "Default")
      (node (ref "U201") (pin "15") (pinfunction "CTS_15") (pintype "passive"))
      (node (ref "U204") (pin "2") (pinfunction "A0_2") (pintype "passive"))
    )
    (net (code "75") (name "/USB_UART_RTS") (class "Default")
      (node (ref "U201") (pin "16") (pinfunction "RTS_16") (pintype "passive"))
      (node (ref "U204") (pin "3") (pinfunction "A1_3") (pintype "passive"))
    )
    (net (code "76") (name "/USB_UART_RXD") (class "Default")
      (node (ref "U201") (pin "18") (pinfunction "TXD_18") (pintype "passive"))
      (node (ref "U204") (pin "5") (pinfunction "A3_5") (pintype "passive"))
    )
    (net (code "77") (name "/USB_UART_TXD") (class "Default")
      (node (ref "U201") (pin "17") (pinfunction "RXD_17") (pintype "passive"))
      (node (ref "U204") (pin "4") (pinfunction "A2_4") (pintype "passive"))
    )
    (net (code "78") (name "DGND") (class "Default")
      (node (ref "C201") (pin "2") (pinfunction "2_2") (pintype "passive"))
      (node (ref "C202") (pin "2") (pinfunction "2_2") (pintype "passive"))
      (node (ref "C203") (pin "2") (pinfunction "2_2") (pintype "passive"))
      (node (ref "C204") (pin "2") (pinfunction "2_2") (pintype "passive"))
      (node (ref "C205") (pin "2") (pinfunction "2_2") (pintype "passive"))
      (node (ref "C206") (pin "2") (pinfunction "2_2") (pintype "passive"))
      (node (ref "C207") (pin "2") (pinfunction "2_2") (pintype "passive"))
      (node (ref "C208") (pin "2") (pinfunction "2_2") (pintype "passive"))
      (node (ref "C209") (pin "2") (pinfunction "2_2") (pintype "passive"))
      (node (ref "C210") (pin "2") (pinfunction "2_2") (pintype "passive"))
      (node (ref "C211") (pin "2") (pinfunction "2_2") (pintype "passive"))
      (node (ref "C212") (pin "2") (pinfunction "2_2") (pintype "passive"))
      (node (ref "C214") (pin "2") (pinfunction "2_2") (pintype "passive"))
      (node (ref "C215") (pin "2") (pinfunction "2_2") (pintype "passive"))
      (node (ref "C216") (pin "2") (pinfunction "2_2") (pintype "passive"))
      (node (ref "C217") (pin "2") (pinfunction "2_2") (pintype "passive"))
      (node (ref "C218") (pin "2") (pinfunction "2_2") (pintype "passive"))
      (node (ref "J201") (pin "15") (pinfunction "15_15") (pintype "passive"))
      (node (ref "J201") (pin "2") (pinfunction "2_2") (pintype "passive"))
      (node (ref "J202") (pin "2") (pinfunction "2_2") (pintype "passive"))
      (node (ref "J203") (pin "2") (pinfunction "2_2") (pintype "passive"))
      (node (ref "J204") (pin "C5") (pinfunction "GND_C5") (pintype "passive"))
      (node (ref "J204") (pin "T6") (pinfunction "VSS_T6") (pintype "passive"))
      (node (ref "Q201") (pin "2") (pinfunction "S_2") (pintype "passive"))
      (node (ref "R202") (pin "2") (pinfunction "2_2") (pintype "passive"))
      (node (ref "R210") (pin "2") (pinfunction "2_2") (pintype "passive"))
      (node (ref "TP222") (pin "1") (pinfunction "1_1") (pintype "passive"))
      (node (ref "TP227") (pin "1") (pinfunction "1_1") (pintype "passive"))
      (node (ref "U201") (pin "12") (pinfunction "GND_12") (pintype "passive"))
      (node (ref "U201") (pin "21") (pinfunction "GND_21") (pintype "passive"))
      (node (ref "U201") (pin "3") (pinfunction "GND_3") (pintype "passive"))
      (node (ref "U202") (pin "C7") (pinfunction "GND_C7") (pintype "passive"))
      (node (ref "U202") (pin "F8") (pinfunction "GND_F8") (pintype "passive"))
      (node (ref "U202") (pin "H4") (pinfunction "GND_H4") (pintype "passive"))
      (node (ref "U203") (pin "7") (pinfunction "GND_7") (pintype "passive"))
      (node (ref "U204") (pin "6") (pinfunction "GND_6") (pintype "passive"))
      (node (ref "U205") (pin "6") (pinfunction "GND_6") (pintype "passive"))
      (node (ref "U206") (pin "17") (pinfunction "GND_17") (pintype "passive"))
      (node (ref "U206") (pin "18") (pinfunction "GND_18") (pintype "passive"))
      (node (ref "U206") (pin "2") (pinfunction "GND_2") (pintype "passive"))
      (node (ref "U206") (pin "29") (pinfunction "GND_29") (pintype "passive"))
      (node (ref "U206") (pin "39") (pinfunction "GND_39") (pintype "passive"))
      (node (ref "U206") (pin "45") (pinfunction "GND_45") (pintype "passive"))
      (node (ref "U206") (pin "46") (pinfunction "GND_46") (pintype "passive"))
      (node (ref "U206") (pin "54") (pinfunction "GND_54") (pintype "passive"))
      (node (ref "U206") (pin "58") (pinfunction "GND_58") (pintype "passive"))
      (node (ref "U206") (pin "59") (pinfunction "GND_59") (pintype "passive"))
      (node (ref "U206") (pin "61") (pinfunction "GND_61") (pintype "passive"))
      (node (ref "U206") (pin "62") (pinfunction "GND_62") (pintype "passive"))
      (node (ref "U206") (pin "63") (pinfunction "GND_63") (pintype "passive"))
      (node (ref "U206") (pin "64") (pinfunction "GND_64") (pintype "passive"))
      (node (ref "U206") (pin "65") (pinfunction "GND_65") (pintype "passive"))
    )
    (net (code "79") (name "Net-(C213-Pad2)") (class "Default")
      (node (ref "C213") (pin "2") (pinfunction "2_2") (pintype "passive"))
      (node (ref "C215") (pin "1") (pinfunction "1_1") (pintype "passive"))
      (node (ref "J202") (pin "1") (pinfunction "1_1") (pintype "passive"))
      (node (ref "L201") (pin "2") (pinfunction "2_2") (pintype "passive"))
    )
    (net (code "80") (name "Net-(C217-Pad1)") (class "Default")
      (node (ref "C217") (pin "1") (pinfunction "1_1") (pintype "passive"))
      (node (ref "J203") (pin "1") (pinfunction "1_1") (pintype "passive"))
      (node (ref "L202") (pin "2") (pinfunction "2_2") (pintype "passive"))
    )
    (net (code "81") (name "Net-(D201-Pad1)") (class "Default")
      (node (ref "D201") (pin "1") (pinfunction "1_1") (pintype "passive"))
      (node (ref "R207") (pin "1") (pinfunction "1_1") (pintype "passive"))
    )
    (net (code "82") (name "Net-(D202-Pad1)") (class "Default")
      (node (ref "D202") (pin "1") (pinfunction "1_1") (pintype "passive"))
      (node (ref "R208") (pin "1") (pinfunction "1_1") (pintype "passive"))
    )
    (net (code "83") (name "Net-(D203-Pad1)") (class "Default")
      (node (ref "D203") (pin "1") (pinfunction "1_1") (pintype "passive"))
      (node (ref "R209") (pin "1") (pinfunction "1_1") (pintype "passive"))
    )
    (net (code "84") (name "Net-(L201-Pad1)") (class "Default")
      (node (ref "L201") (pin "1") (pinfunction "1_1") (pintype "passive"))
      (node (ref "R206") (pin "2") (pinfunction "2_2") (pintype "passive"))
    )
    (net (code "85") (name "Net-(Q201-D)") (class "Default")
      (node (ref "Q201") (pin "3") (pinfunction "D_3") (pintype "passive"))
      (node (ref "TP223") (pin "1") (pinfunction "1_1") (pintype "passive"))
      (node (ref "U206") (pin "1") (pinfunction "PWRKEY_1") (pintype "passive"))
    )
    (net (code "86") (name "Net-(U201-VBUS)") (class "Default")
      (node (ref "R201") (pin "2") (pinfunction "2_2") (pintype "passive"))
      (node (ref "R202") (pin "1") (pinfunction "1_1") (pintype "passive"))
      (node (ref "U201") (pin "8") (pinfunction "VBUS_8") (pintype "passive"))
    )
    (net (code "87") (name "Net-(U201-VDD)") (class "Default")
      (node (ref "R203") (pin "1") (pinfunction "1_1") (pintype "passive"))
      (node (ref "U201") (pin "6") (pinfunction "VDD_6") (pintype "passive"))
    )
    (net (code "88") (name "Net-(U201-~{RST})") (class "Default")
      (node (ref "R203") (pin "2") (pinfunction "2_2") (pintype "passive"))
      (node (ref "U201") (pin "9") (pinfunction "~{RST}_9") (pintype "passive"))
    )
    (net (code "89") (name "Net-(U203-VBACKUP)") (class "Default")
      (node (ref "C210") (pin "1") (pinfunction "1_1") (pintype "passive"))
      (node (ref "U203") (pin "8") (pinfunction "VBACKUP_8") (pintype "passive"))
    )
    (net (code "90") (name "Net-(U206-GNSS_ANT)") (class "Default")
      (node (ref "C213") (pin "1") (pinfunction "1_1") (pintype "passive"))
      (node (ref "C214") (pin "1") (pinfunction "1_1") (pintype "passive"))
      (node (ref "U206") (pin "53") (pinfunction "GNSS_ANT_53") (pintype "passive"))
    )
    (net (code "91") (name "Net-(U206-RF_ANT)") (class "Default")
      (node (ref "C216") (pin "1") (pinfunction "1_1") (pintype "passive"))
      (node (ref "L202") (pin "1") (pinfunction "1_1") (pintype "passive"))
      (node (ref "U206") (pin "60") (pinfunction "RF_ANT_60") (pintype "passive"))
    )
    (net (code "92") (name "Net-(U206-USB_VBUS)") (class "Default")
      (node (ref "TP226") (pin "1") (pinfunction "1_1") (pintype "passive"))
      (node (ref "U206") (pin "24") (pinfunction "USB_VBUS_24") (pintype "passive"))
    )
    (net (code "93") (name "unconnected-(J204A-VPP-PadC6)") (class "Default")
      (node (ref "J204") (pin "C6") (pinfunction "VPP_C6") (pintype "passive+no_connect"))
    )
    (net (code "94") (name "unconnected-(J204B-CARD_DETECT-PadSW)") (class "Default")
      (node (ref "J204") (pin "SW") (pinfunction "CARD_DETECT_SW") (pintype "passive+no_connect"))
    )
    (net (code "95") (name "unconnected-(J204B-DAT1-PadT8)") (class "Default")
      (node (ref "J204") (pin "T8") (pinfunction "DAT1_T8") (pintype "passive+no_connect"))
    )
    (net (code "96") (name "unconnected-(J204B-DAT2-PadT1)") (class "Default")
      (node (ref "J204") (pin "T1") (pinfunction "DAT2_T1") (pintype "passive+no_connect"))
    )
    (net (code "97") (name "unconnected-(U201-GPIO0{slash}CLK-Pad2)") (class "Default")
      (node (ref "U201") (pin "2") (pinfunction "GPIO0/CLK_2") (pintype "passive+no_connect"))
    )
    (net (code "98") (name "unconnected-(U201-GPIO1{slash}RS485-Pad1)") (class "Default")
      (node (ref "U201") (pin "1") (pinfunction "GPIO1/RS485_1") (pintype "passive+no_connect"))
    )
    (net (code "99") (name "unconnected-(U201-GPIO2{slash}TXT-Pad20)") (class "Default")
      (node (ref "U201") (pin "20") (pinfunction "GPIO2/TXT_20") (pintype "passive+no_connect"))
    )
    (net (code "100") (name "unconnected-(U201-GPIO3{slash}RXT-Pad19)") (class "Default")
      (node (ref "U201") (pin "19") (pinfunction "GPIO3/RXT_19") (pintype "passive+no_connect"))
    )
    (net (code "101") (name "unconnected-(U201-SUSPEND-Pad14)") (class "Default")
      (node (ref "U201") (pin "14") (pinfunction "SUSPEND_14") (pintype "passive+no_connect"))
    )
    (net (code "102") (name "unconnected-(U201-WAKEUP-Pad13)") (class "Default")
      (node (ref "U201") (pin "13") (pinfunction "WAKEUP_13") (pintype "passive+no_connect"))
    )
    (net (code "103") (name "unconnected-(U201-~{SUSPEND}-Pad11)") (class "Default")
      (node (ref "U201") (pin "11") (pinfunction "~{SUSPEND}_11") (pintype "passive+no_connect"))
    )
    (net (code "104") (name "unconnected-(U202A-I{slash}O-PadC4)") (class "Default")
      (node (ref "U202") (pin "C4") (pinfunction "I/O_C4") (pintype "passive+no_connect"))
    )
    (net (code "105") (name "unconnected-(U202A-I{slash}O-PadC5)") (class "Default")
      (node (ref "U202") (pin "C5") (pinfunction "I/O_C5") (pintype "passive+no_connect"))
    )
    (net (code "106") (name "unconnected-(U202A-I{slash}O-PadC8)") (class "Default")
      (node (ref "U202") (pin "C8") (pinfunction "I/O_C8") (pintype "passive+no_connect"))
    )
    (net (code "107") (name "unconnected-(U202A-I{slash}O-PadD8)") (class "Default")
      (node (ref "U202") (pin "D8") (pinfunction "I/O_D8") (pintype "passive+no_connect"))
    )
    (net (code "108") (name "unconnected-(U202A-I{slash}O-PadE8)") (class "Default")
      (node (ref "U202") (pin "E8") (pinfunction "I/O_E8") (pintype "passive+no_connect"))
    )
    (net (code "109") (name "unconnected-(U202A-I{slash}O-PadF3)") (class "Default")
      (node (ref "U202") (pin "F3") (pinfunction "I/O_F3") (pintype "passive+no_connect"))
    )
    (net (code "110") (name "unconnected-(U202A-I{slash}O-PadG3)") (class "Default")
      (node (ref "U202") (pin "G3") (pinfunction "I/O_G3") (pintype "passive+no_connect"))
    )
    (net (code "111") (name "unconnected-(U202A-I{slash}O-PadH3)") (class "Default")
      (node (ref "U202") (pin "H3") (pinfunction "I/O_H3") (pintype "passive+no_connect"))
    )
    (net (code "112") (name "unconnected-(U202A-I{slash}O-PadH5)") (class "Default")
      (node (ref "U202") (pin "H5") (pinfunction "I/O_H5") (pintype "passive+no_connect"))
    )
    (net (code "113") (name "unconnected-(U202A-I{slash}O-PadH7)") (class "Default")
      (node (ref "U202") (pin "H7") (pinfunction "I/O_H7") (pintype "passive+no_connect"))
    )
    (net (code "114") (name "unconnected-(U202A-I{slash}O-PadH8)") (class "Default")
      (node (ref "U202") (pin "H8") (pinfunction "I/O_H8") (pintype "passive+no_connect"))
    )
    (net (code "115") (name "unconnected-(U203-CLKOUT-Pad5)") (class "Default")
      (node (ref "U203") (pin "5") (pinfunction "CLKOUT_5") (pintype "passive+no_connect"))
    )
    (net (code "116") (name "unconnected-(U203-INT2-Pad6)") (class "Default")
      (node (ref "U203") (pin "6") (pinfunction "INT2_6") (pintype "passive+no_connect"))
    )
    (net (code "117") (name "unconnected-(U206-CTS-Pad7)") (class "Default")
      (node (ref "U206") (pin "7") (pinfunction "CTS_7") (pintype "passive+no_connect"))
    )
    (net (code "118") (name "unconnected-(U206-DCD-Pad5)") (class "Default")
      (node (ref "U206") (pin "5") (pinfunction "DCD_5") (pintype "passive+no_connect"))
    )
    (net (code "119") (name "unconnected-(U206-DTR-Pad3)") (class "Default")
      (node (ref "U206") (pin "3") (pinfunction "DTR_3") (pintype "passive+no_connect"))
    )
    (net (code "120") (name "unconnected-(U206-GPIO0{slash}UART3_TXD-Pad50)") (class "Default")
      (node (ref "U206") (pin "50") (pinfunction "GPIO0/UART3_TXD_50") (pintype "passive+no_connect"))
    )
    (net (code "121") (name "unconnected-(U206-GPIO1{slash}UART3_RXD-Pad49)") (class "Default")
      (node (ref "U206") (pin "49") (pinfunction "GPIO1/UART3_RXD_49") (pintype "passive+no_connect"))
    )
    (net (code "122") (name "unconnected-(U206-GPIO2-Pad67)") (class "Default")
      (node (ref "U206") (pin "67") (pinfunction "GPIO2_67") (pintype "passive+no_connect"))
    )
    (net (code "123") (name "unconnected-(U206-GPIO3-Pad68)") (class "Default")
      (node (ref "U206") (pin "68") (pinfunction "GPIO3_68") (pintype "passive+no_connect"))
    )
    (net (code "124") (name "unconnected-(U206-I2C_SCL-Pad38)") (class "Default")
      (node (ref "U206") (pin "38") (pinfunction "I2C_SCL_38") (pintype "passive+no_connect"))
    )
    (net (code "125") (name "unconnected-(U206-I2C_SDA-Pad37)") (class "Default")
      (node (ref "U206") (pin "37") (pinfunction "I2C_SDA_37") (pintype "passive+no_connect"))
    )
    (net (code "126") (name "unconnected-(U206-NC-Pad19)") (class "Default")
      (node (ref "U206") (pin "19") (pinfunction "NC_19") (pintype "passive+no_connect"))
    )
    (net (code "127") (name "unconnected-(U206-NC-Pad20)") (class "Default")
      (node (ref "U206") (pin "20") (pinfunction "NC_20") (pintype "passive+no_connect"))
    )
    (net (code "128") (name "unconnected-(U206-NC-Pad21)") (class "Default")
      (node (ref "U206") (pin "21") (pinfunction "NC_21") (pintype "passive+no_connect"))
    )
    (net (code "129") (name "unconnected-(U206-NC-Pad22)") (class "Default")
      (node (ref "U206") (pin "22") (pinfunction "NC_22") (pintype "passive+no_connect"))
    )
    (net (code "130") (name "unconnected-(U206-NC-Pad26)") (class "Default")
      (node (ref "U206") (pin "26") (pinfunction "NC_26") (pintype "passive+no_connect"))
    )
    (net (code "131") (name "unconnected-(U206-NC-Pad35)") (class "Default")
      (node (ref "U206") (pin "35") (pinfunction "NC_35") (pintype "passive+no_connect"))
    )
    (net (code "132") (name "unconnected-(U206-NC-Pad36)") (class "Default")
      (node (ref "U206") (pin "36") (pinfunction "NC_36") (pintype "passive+no_connect"))
    )
    (net (code "133") (name "unconnected-(U206-NC-Pad40)") (class "Default")
      (node (ref "U206") (pin "40") (pinfunction "NC_40") (pintype "passive+no_connect"))
    )
    (net (code "134") (name "unconnected-(U206-NC-Pad41)") (class "Default")
      (node (ref "U206") (pin "41") (pinfunction "NC_41") (pintype "passive+no_connect"))
    )
    (net (code "135") (name "unconnected-(U206-NC-Pad42)") (class "Default")
      (node (ref "U206") (pin "42") (pinfunction "NC_42") (pintype "passive+no_connect"))
    )
    (net (code "136") (name "unconnected-(U206-NC-Pad43)") (class "Default")
      (node (ref "U206") (pin "43") (pinfunction "NC_43") (pintype "passive+no_connect"))
    )
    (net (code "137") (name "unconnected-(U206-NC-Pad44)") (class "Default")
      (node (ref "U206") (pin "44") (pinfunction "NC_44") (pintype "passive+no_connect"))
    )
    (net (code "138") (name "unconnected-(U206-NC-Pad47)") (class "Default")
      (node (ref "U206") (pin "47") (pinfunction "NC_47") (pintype "passive+no_connect"))
    )
    (net (code "139") (name "unconnected-(U206-NC-Pad51)") (class "Default")
      (node (ref "U206") (pin "51") (pinfunction "NC_51") (pintype "passive+no_connect"))
    )
    (net (code "140") (name "unconnected-(U206-RI-Pad4)") (class "Default")
      (node (ref "U206") (pin "4") (pinfunction "RI_4") (pintype "passive+no_connect"))
    )
    (net (code "141") (name "unconnected-(U206-RTS-Pad8)") (class "Default")
      (node (ref "U206") (pin "8") (pinfunction "RTS_8") (pintype "passive+no_connect"))
    )
    (net (code "142") (name "unconnected-(U206-VDD_EXT-Pad15)") (class "Default")
      (node (ref "U206") (pin "15") (pinfunction "VDD_EXT_15") (pintype "passive+no_connect"))
    )
  )
)
